# mantarray_beta2_sensor.net
KiCad netlist of a schematic drawn in Altium Designer
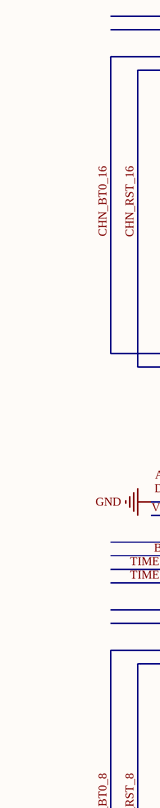
[diagram p0: mantarray_beta2_sensor.SchDoc, top left]
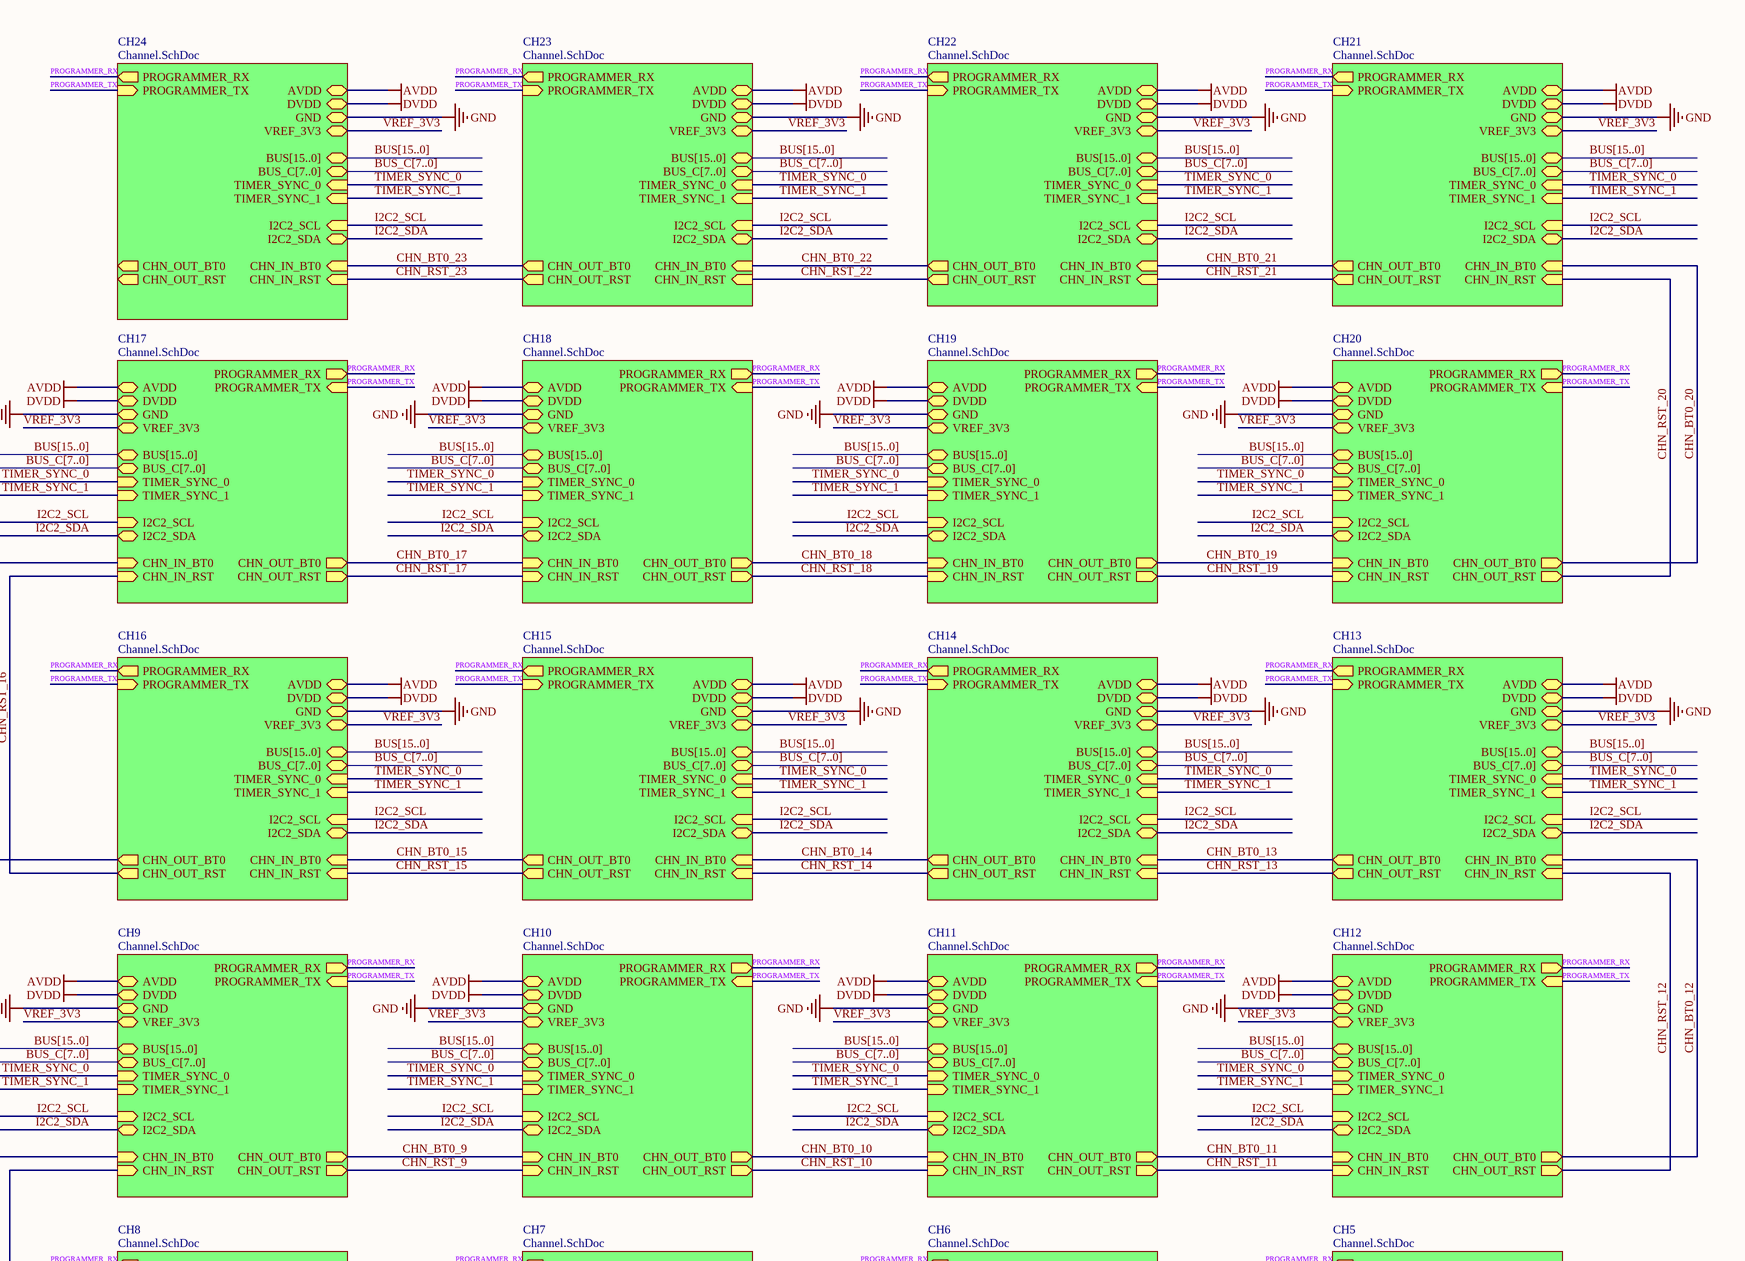
[diagram p1: mantarray_beta2_sensor.SchDoc, top right]
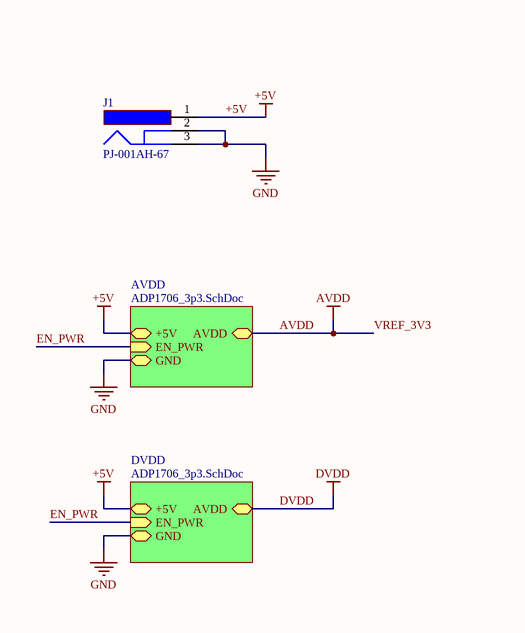
[diagram p2: mantarray_beta2_sensor.SchDoc, bottom left]
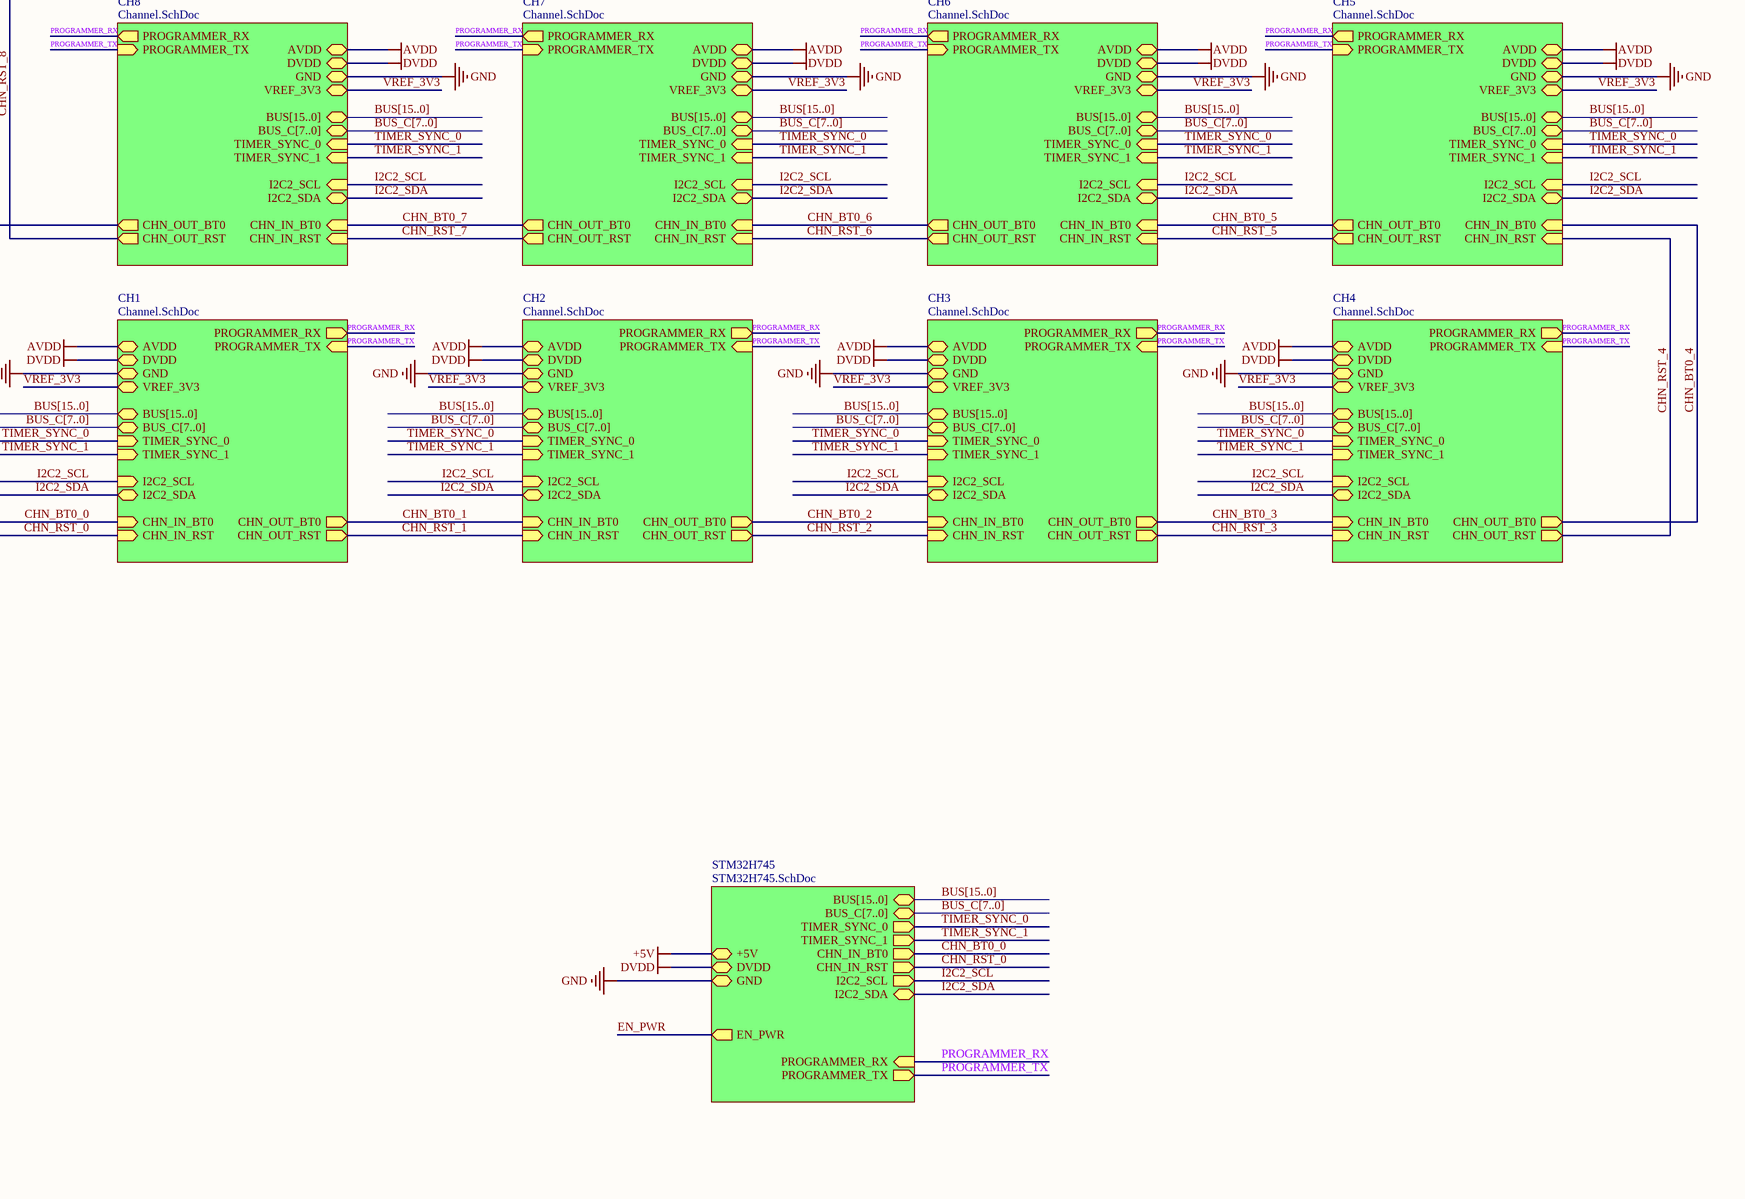
[diagram p3: mantarray_beta2_sensor.SchDoc, bottom right]

(export (version "E")
  (design (tool "Eeschema 10.0.6"))
  (components
    (comp (ref "J1")
      (value "PJ-001AH-67")
      (footprint "PJ-001AH-67")
      (description "IP67 waterproof DC Power Jack")
      (libsource (lib "mantarray_library") (part "PJ-001AH-67"))
    )
  )
  (nets
    (net (code "25") (name "+5V") (class "Default")
      (node (ref "J1") (pin "1") (pinfunction "1_1") (pintype "passive"))
    )
    (net (code "87") (name "GND") (class "Default")
      (node (ref "J1") (pin "2") (pinfunction "2_2") (pintype "passive"))
      (node (ref "J1") (pin "3") (pinfunction "3_3") (pintype "passive"))
    )
  )
)
